# msq_ethrottle_tssop.net
KiCad netlist of a schematic drawn in EasyEDA Pro
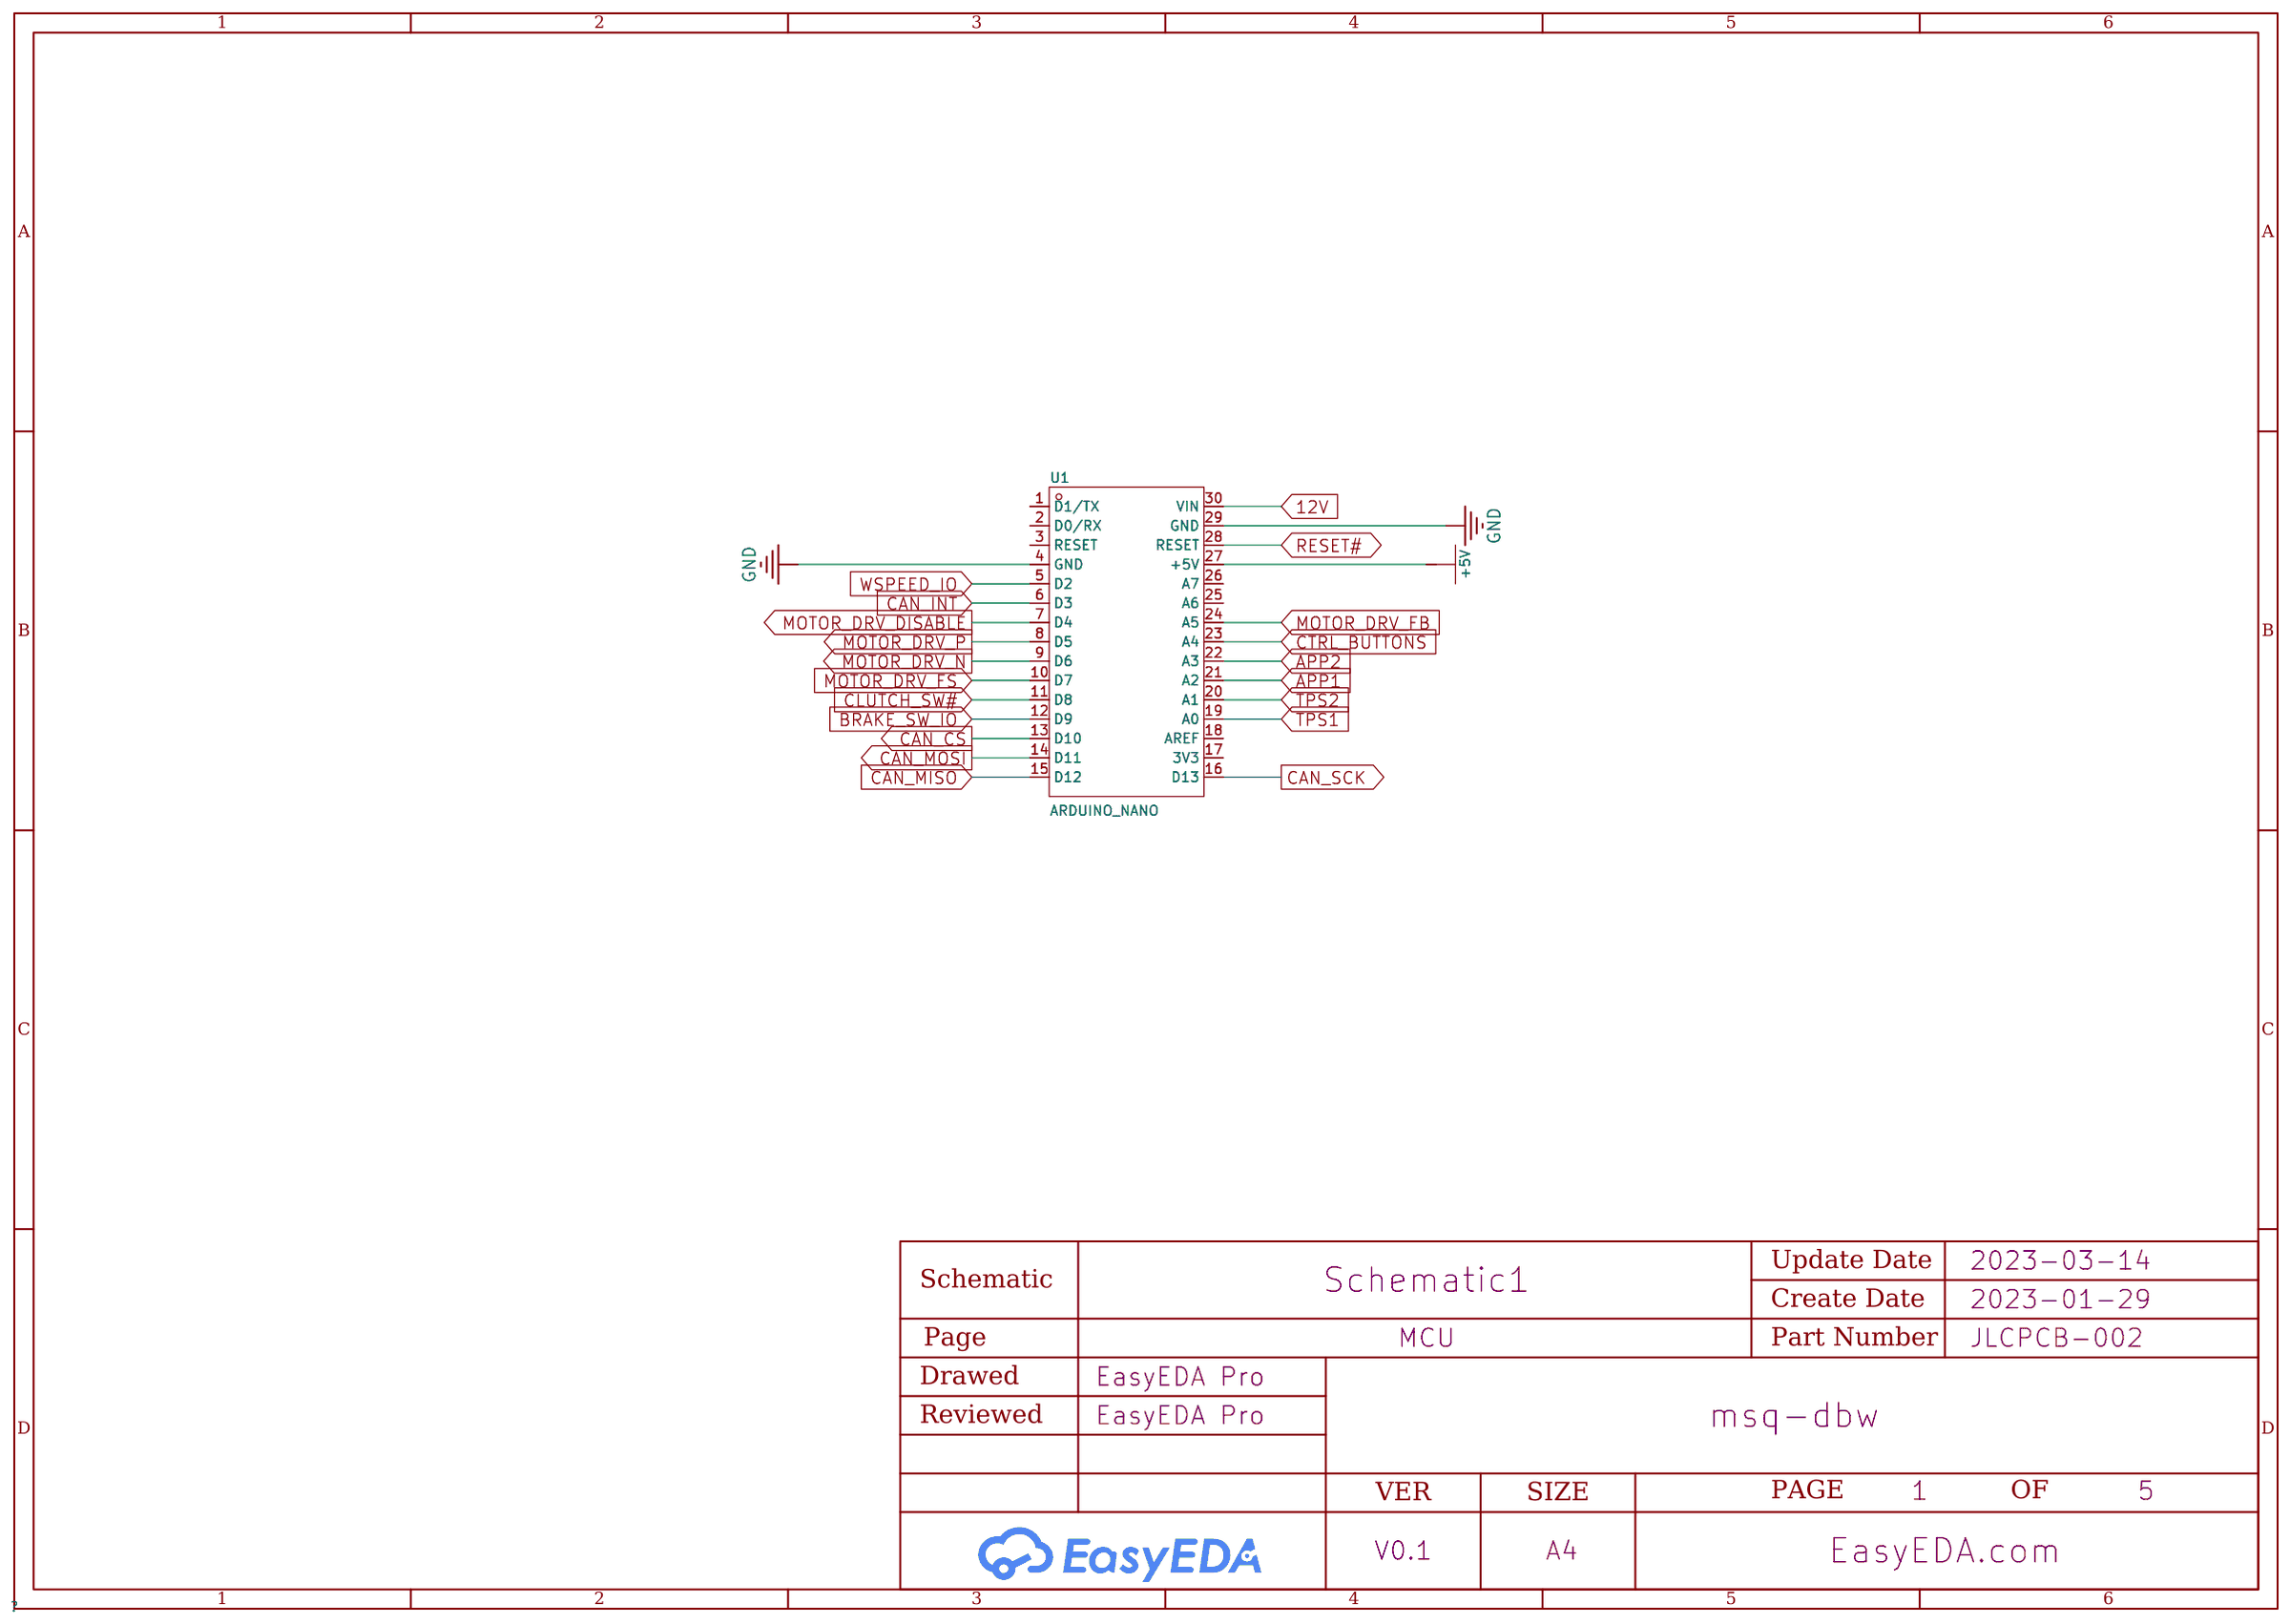
[diagram p0: MCU]
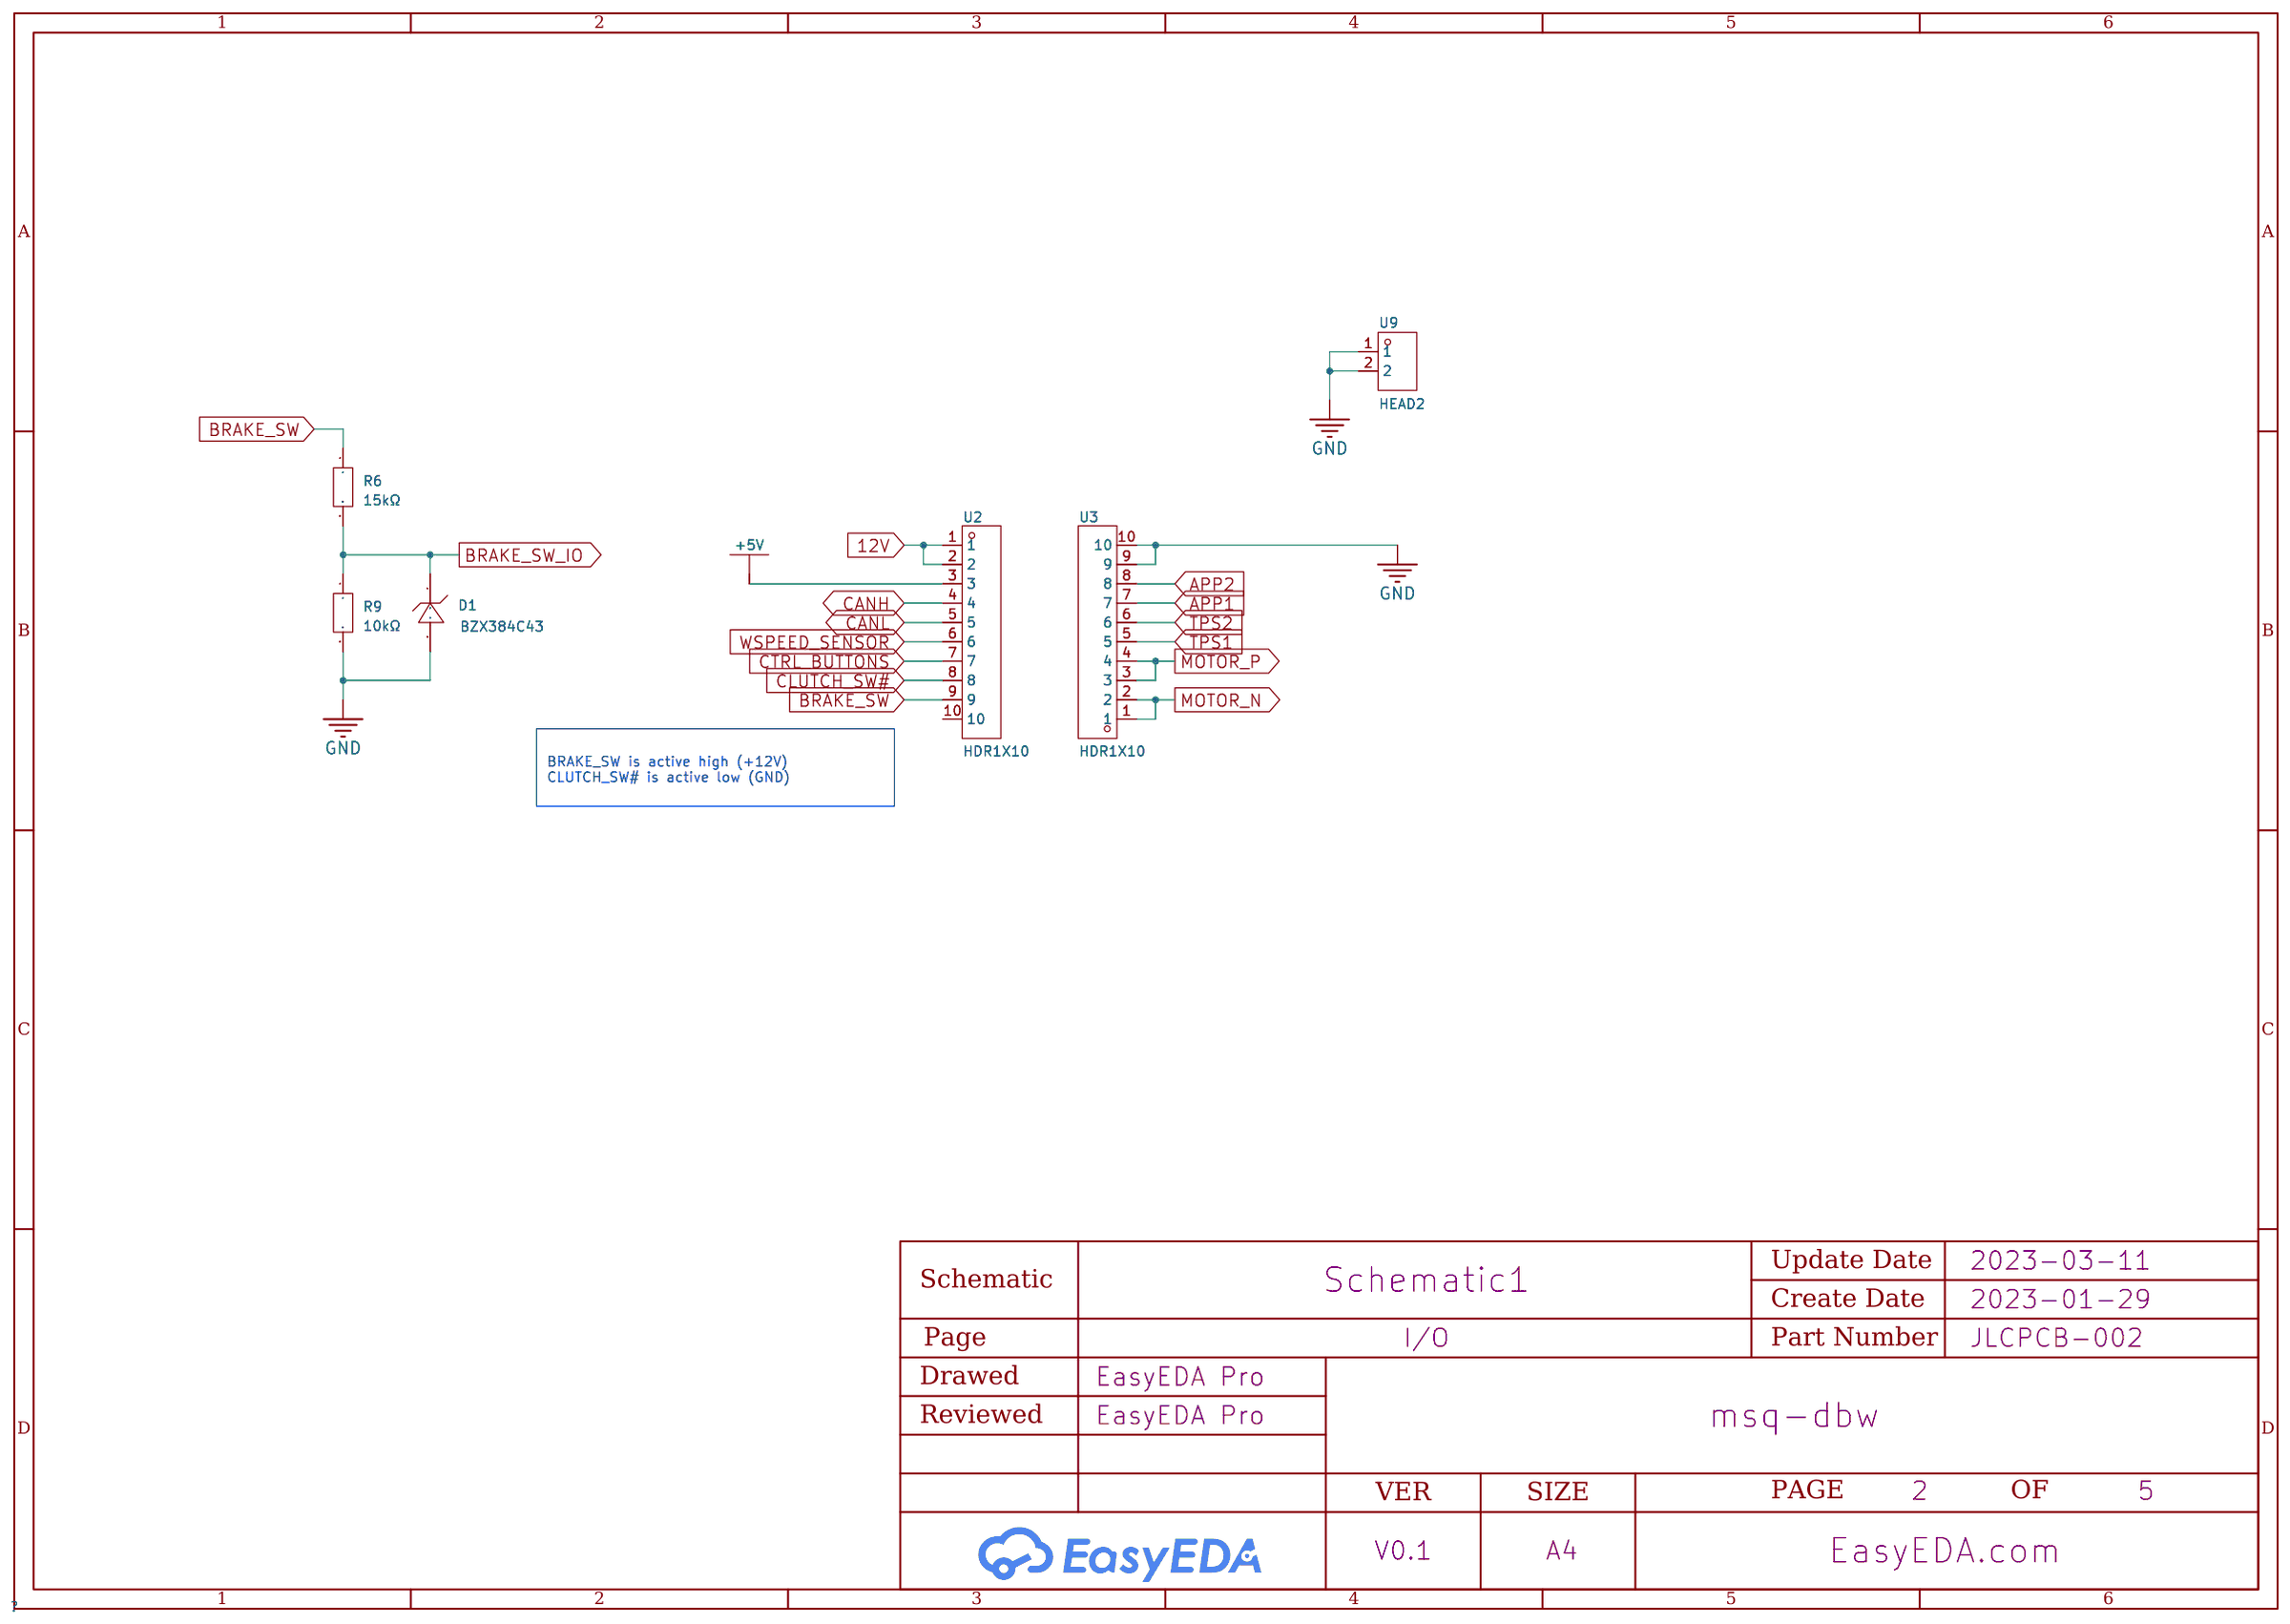
[diagram p1: I/O]
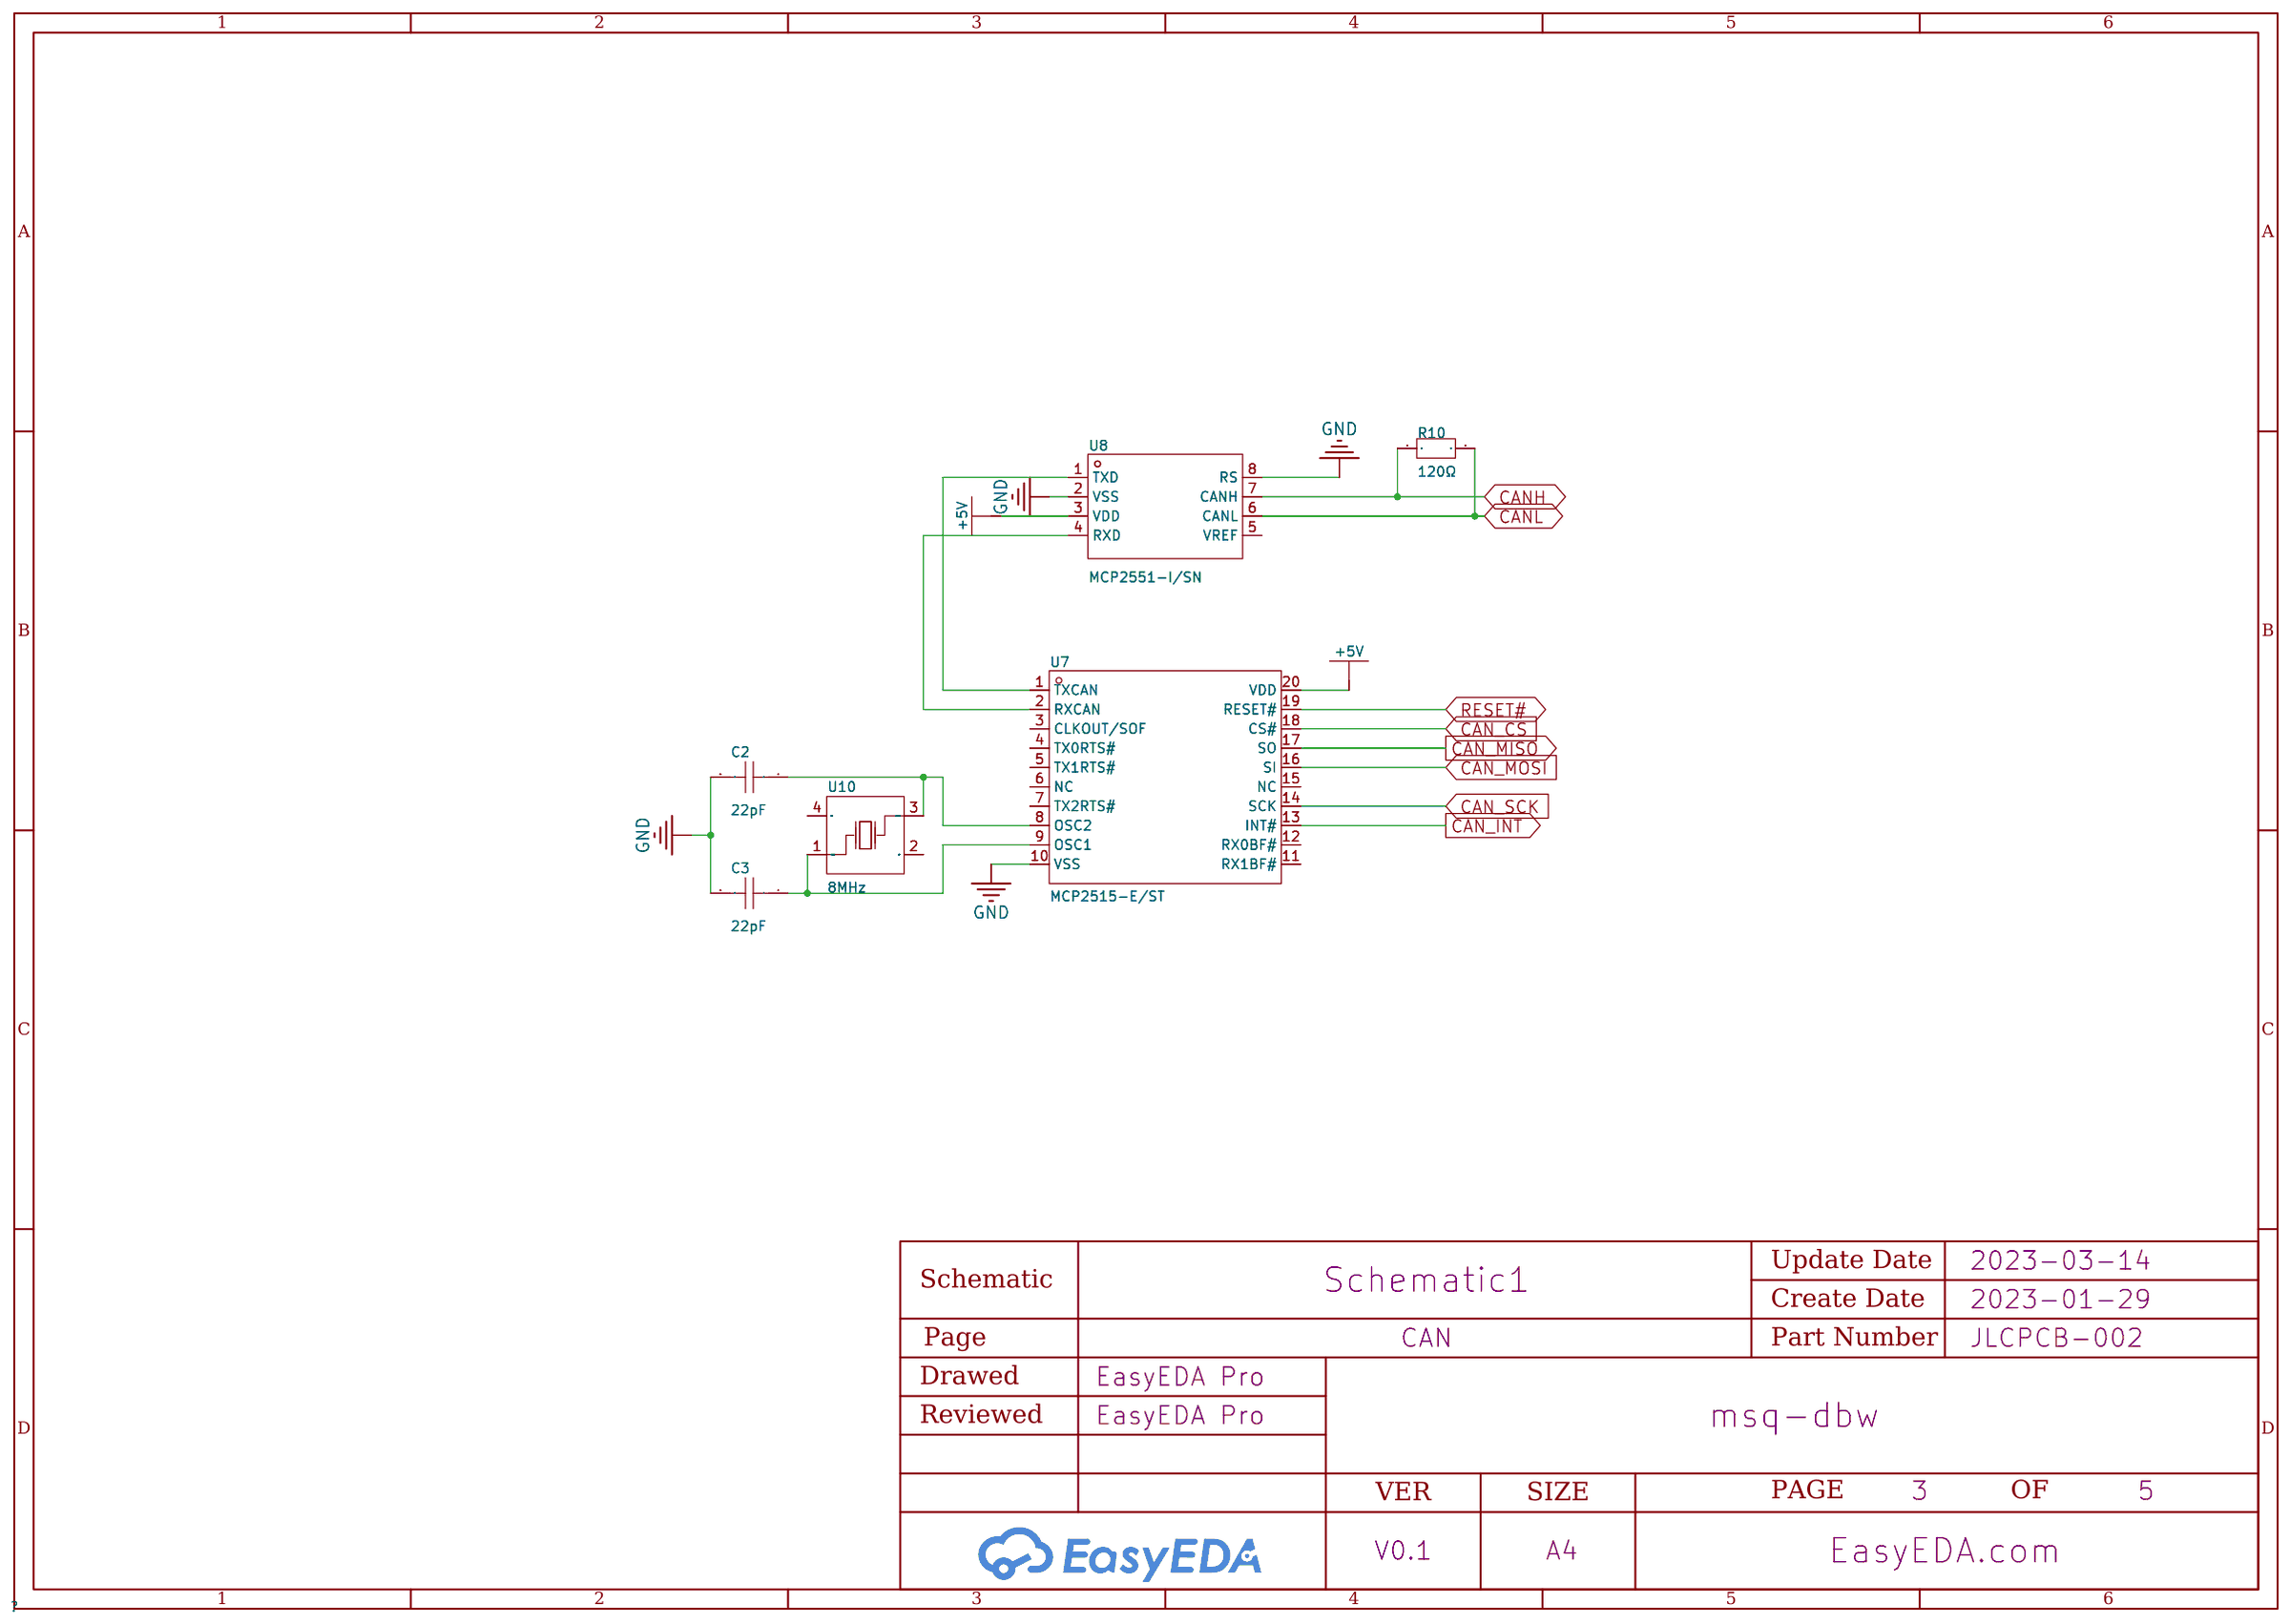
[diagram p2: CAN]
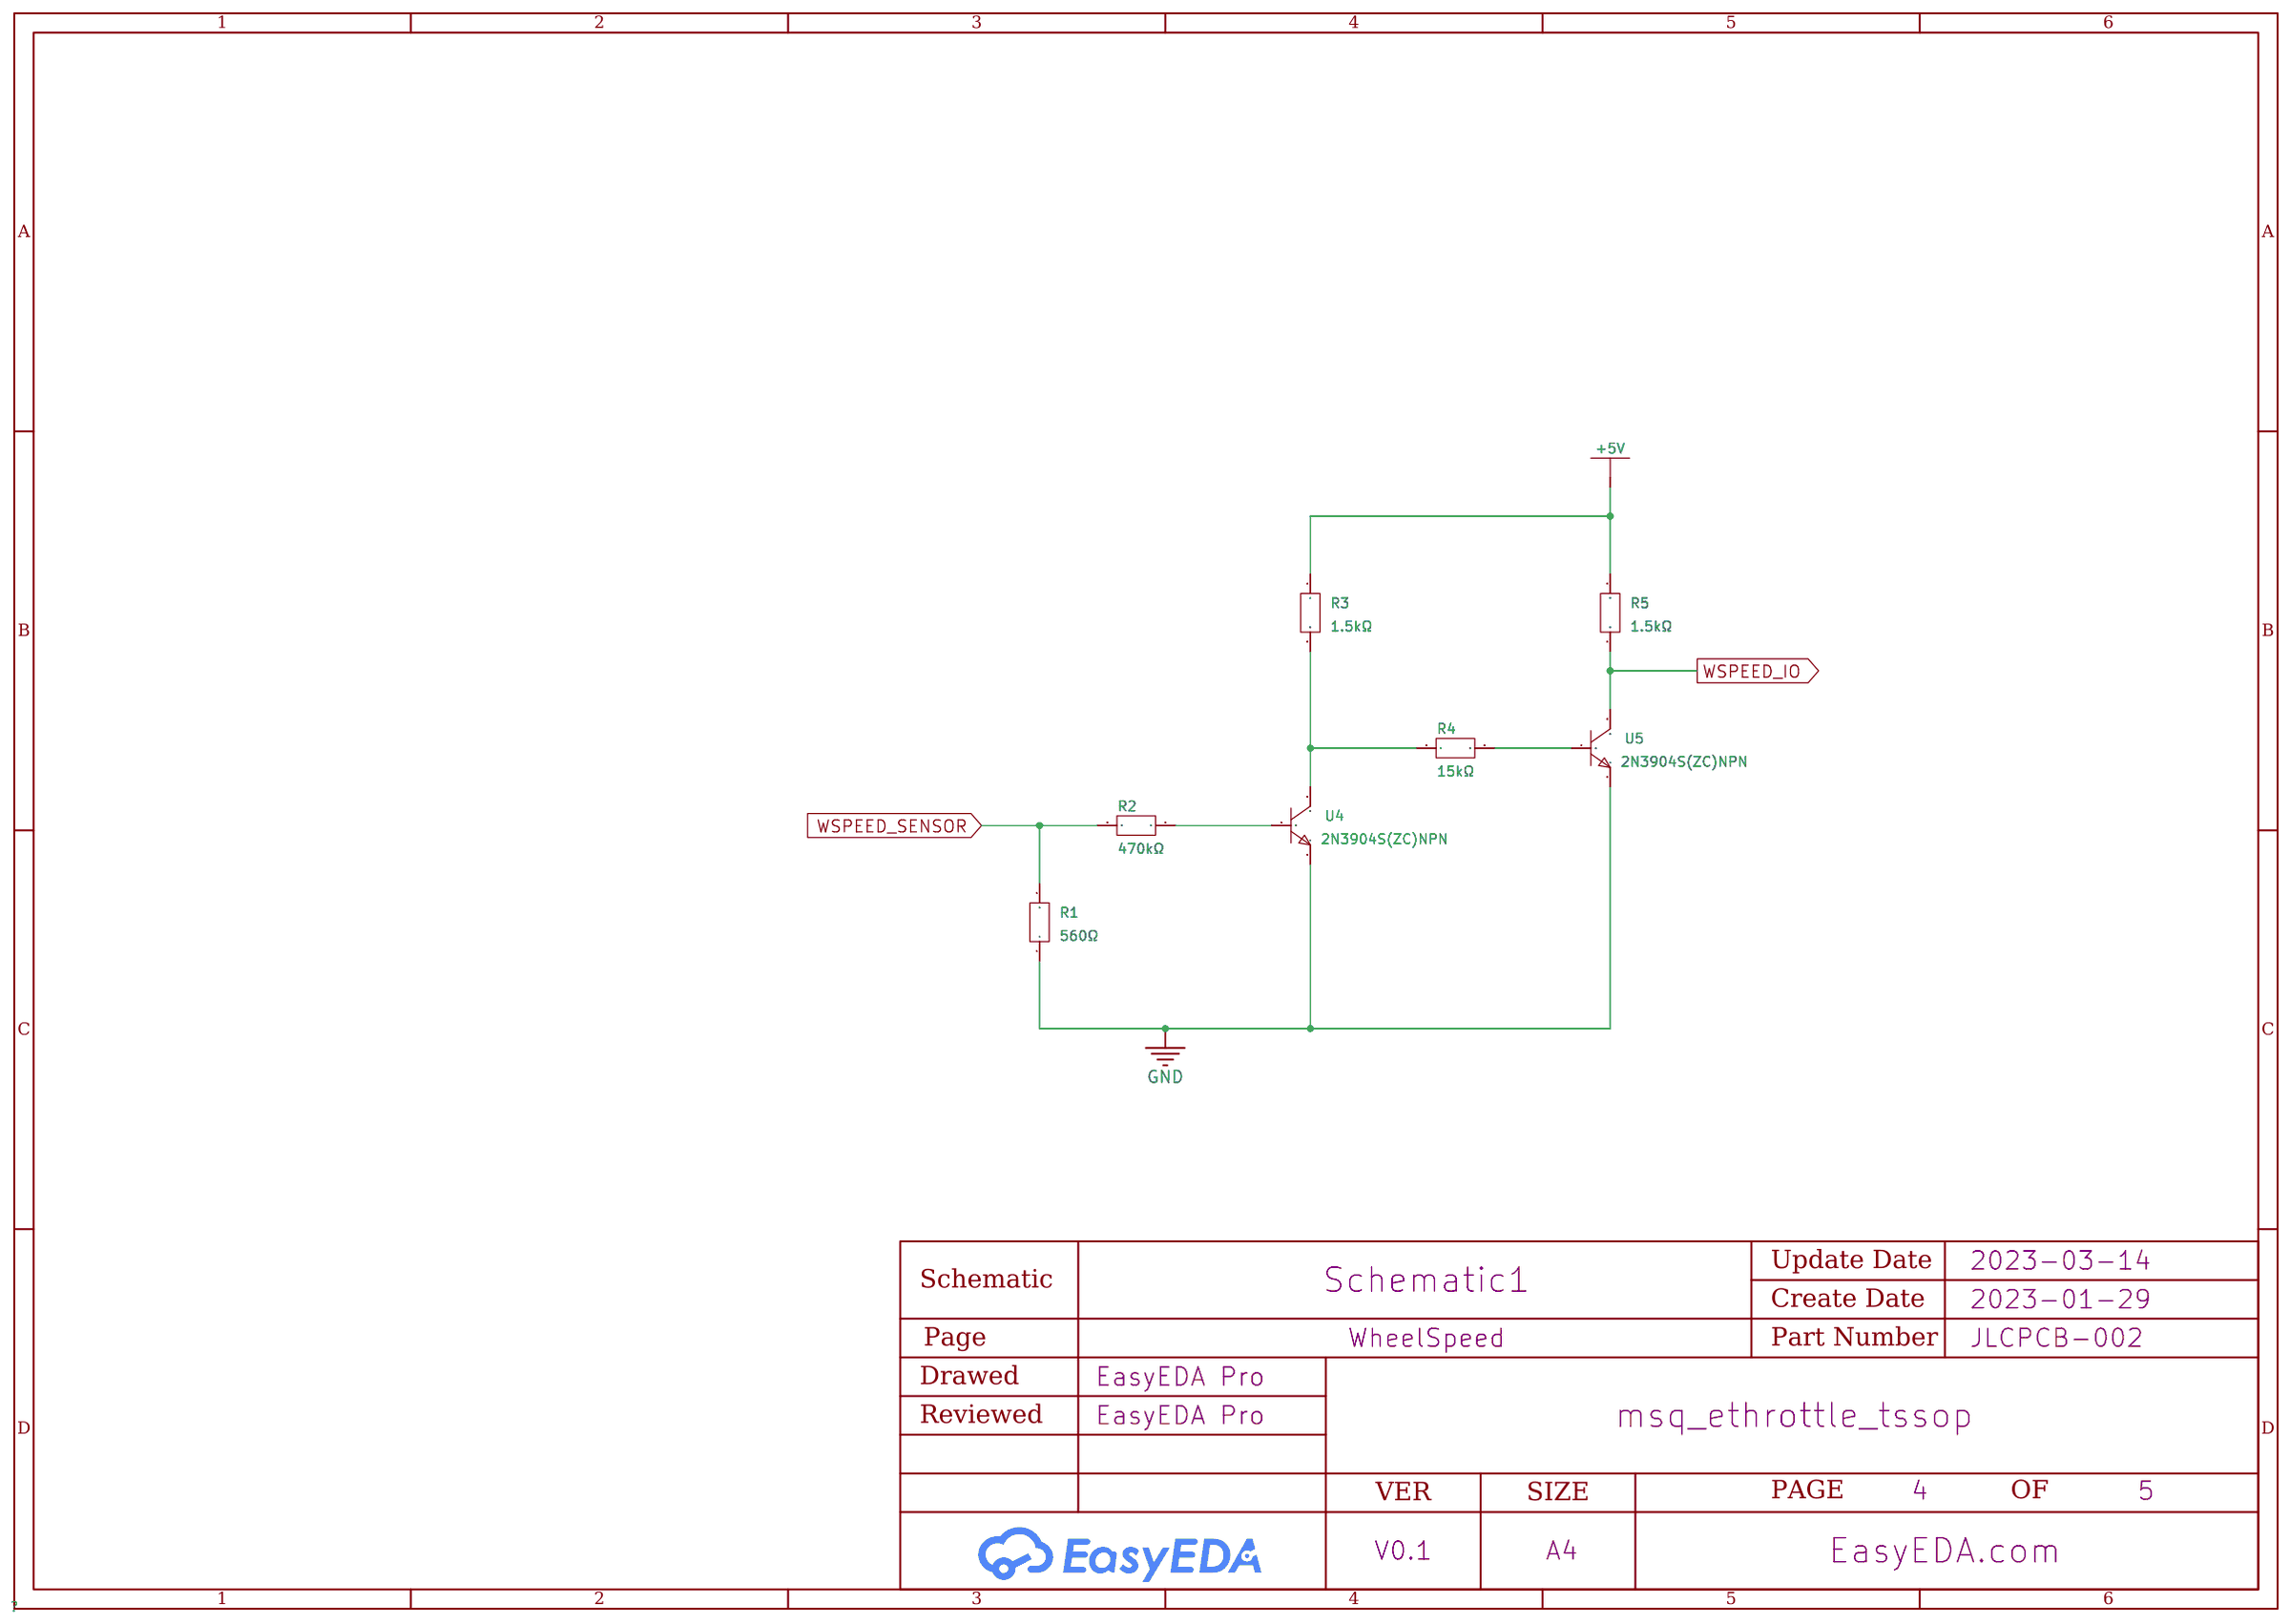
[diagram p3: WheelSpeed]
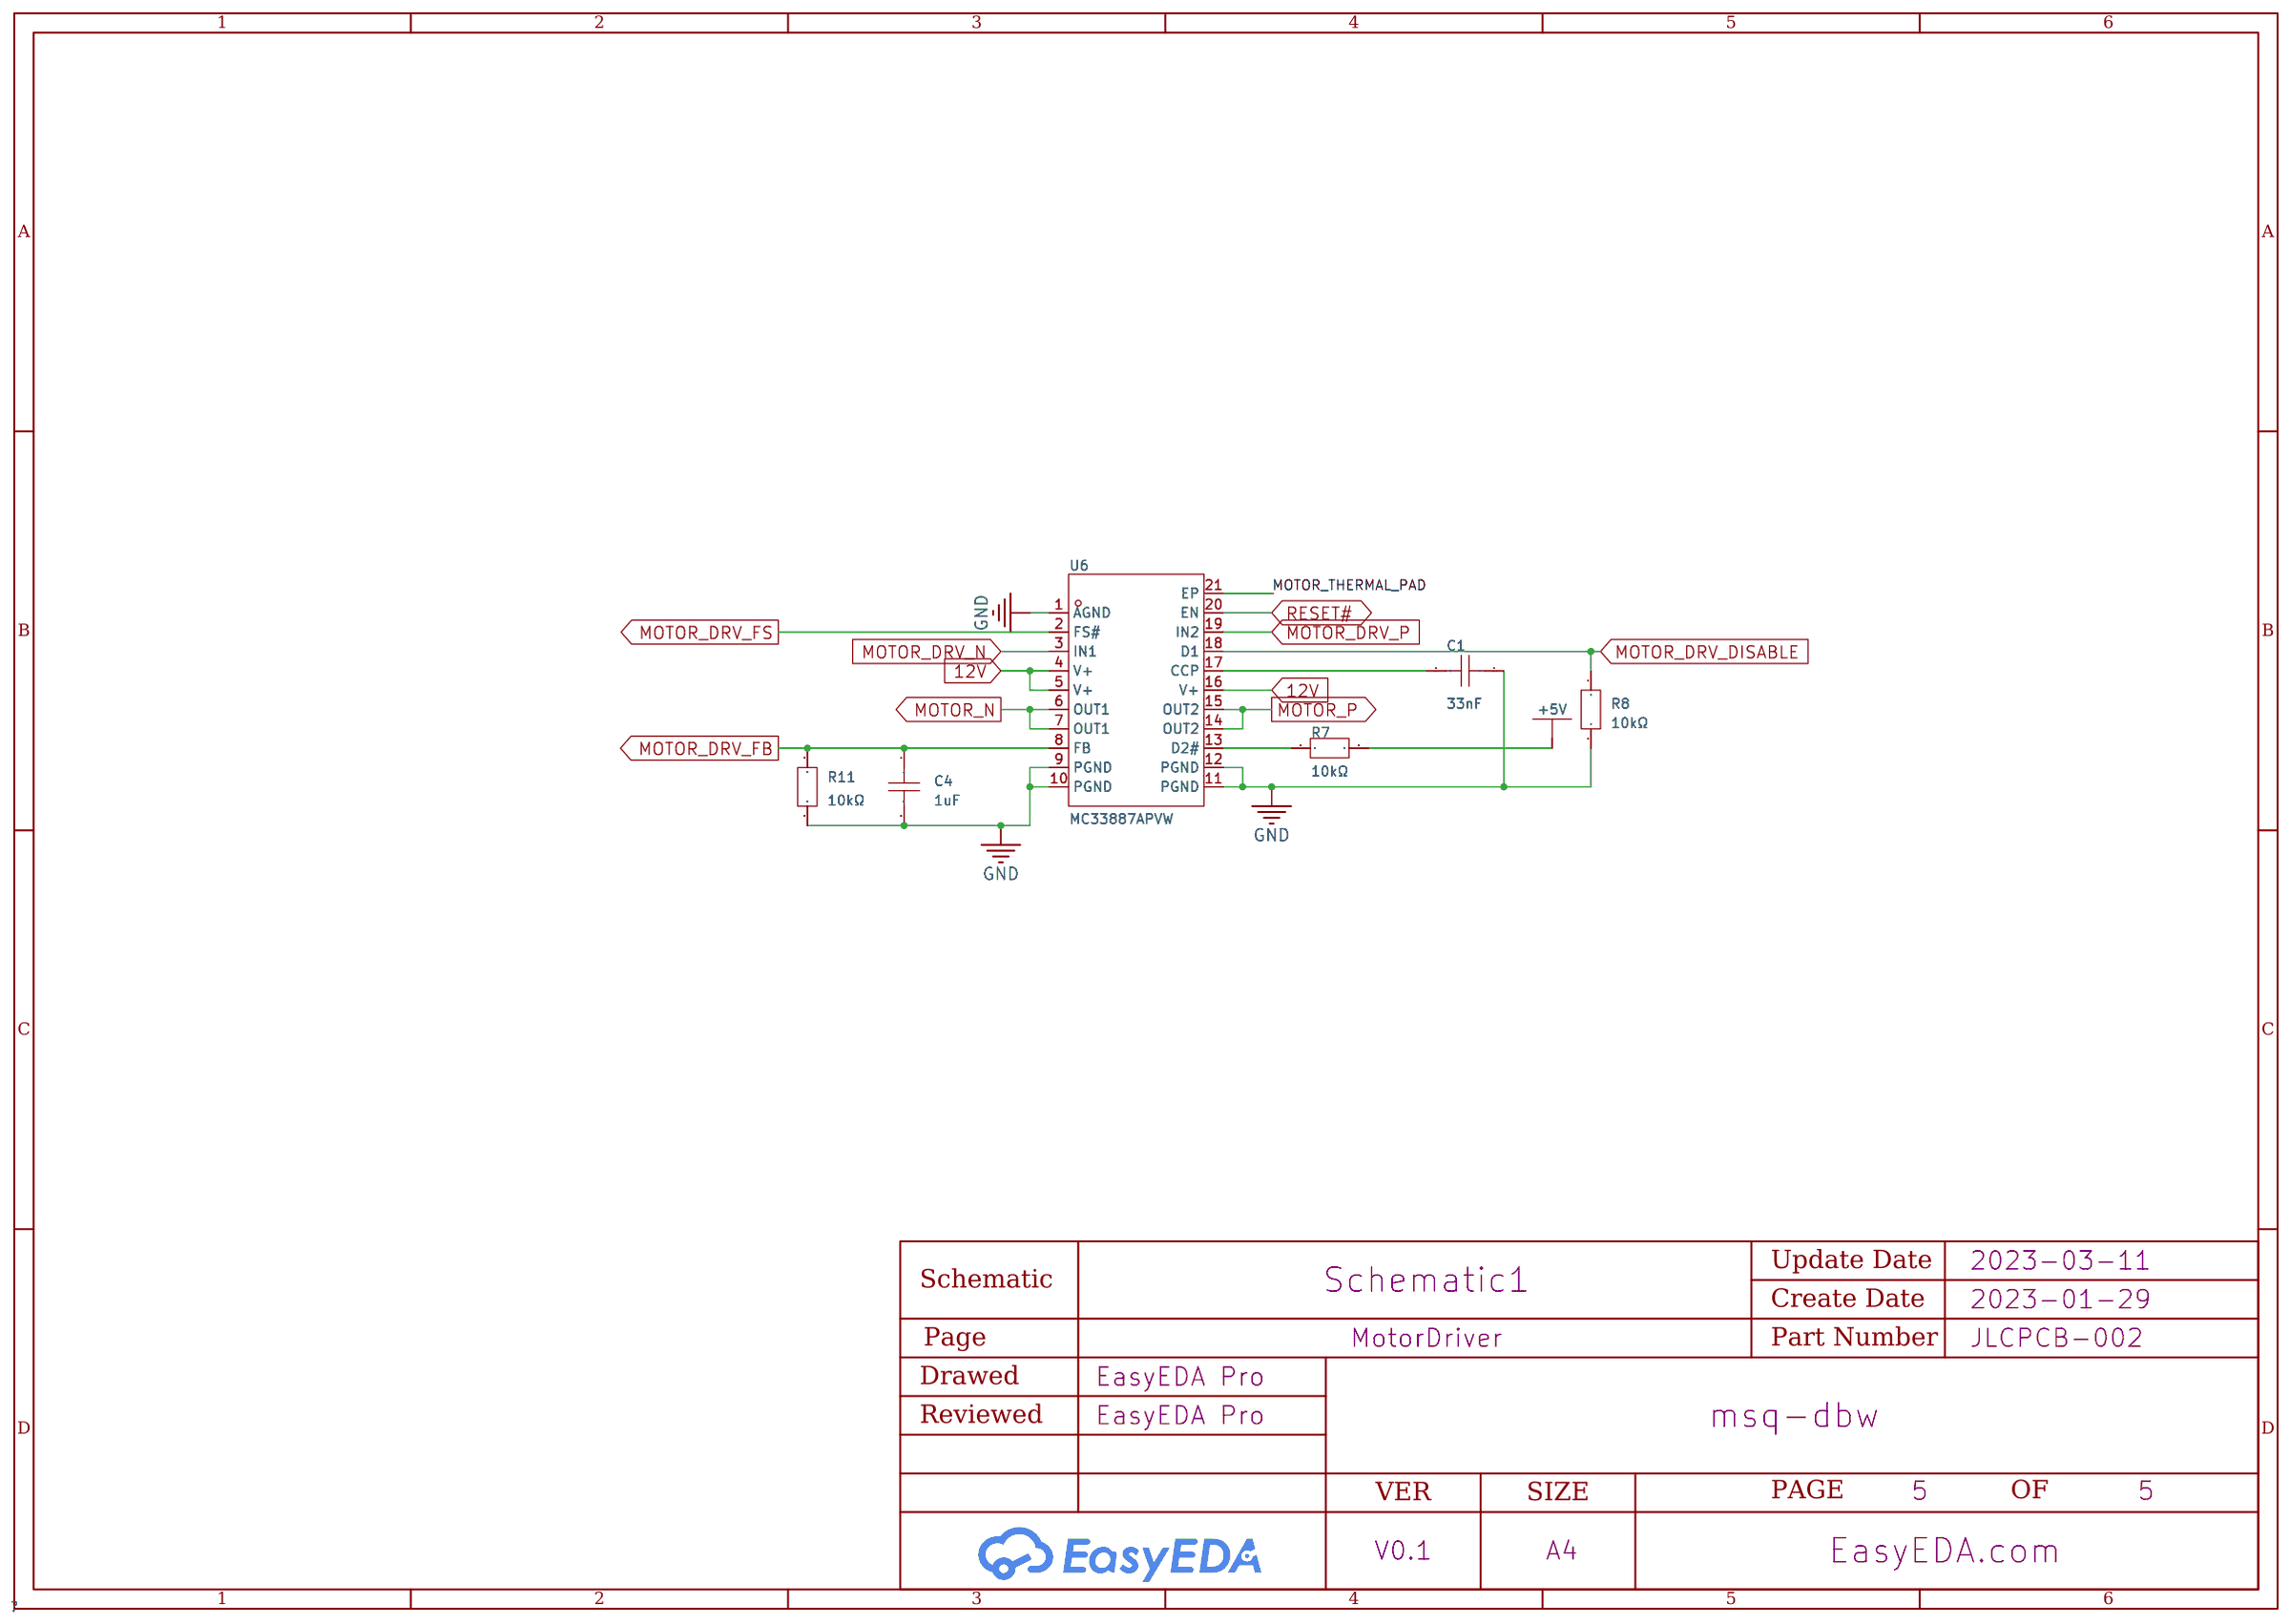
[diagram p4: MotorDriver]

(export (version "E")
  (design (tool "Eeschema 10.0.6"))
  (components
    (comp (ref "U1")
      (value "ARDUINO_NANO")
      (footprint "easyedapro:COMM-TH_ARDUINO_NANO")
      (libsource (lib "easyedapro") (part "ARDUINO_NANO"))
    )
    (comp (ref "D1")
      (value "BZX384C43")
      (footprint "easyedapro:SOD-323_L1.7-W1.3-LS2.6-RD")
      (fields (field (name "Manufacturer") "EIC") (field (name "Tolerance") "±2%"))
      (libsource (lib "easyedapro") (part "BZX384C43"))
    )
    (comp (ref "R6")
      (value "15kΩ")
      (footprint "easyedapro:R0805")
      (fields
        (field (name "Manufacturer Part") "0603WAF1002T5E")
        (field (name "Manufacturer") "UNI-ROYAL(厚声)")
        (field (name "Tolerance") "±1%")
      )
      (libsource (lib "easyedapro") (part "RT0805BRD07360RL"))
    )
    (comp (ref "R9")
      (value "10kΩ")
      (footprint "easyedapro:R0805")
      (fields
        (field (name "Manufacturer Part") "0603WAF1002T5E")
        (field (name "Manufacturer") "UNI-ROYAL(厚声)")
        (field (name "Tolerance") "±1%")
      )
      (libsource (lib "easyedapro") (part "RT0805BRD07360RL"))
    )
    (comp (ref "U2")
      (value "HDR1X10")
      (footprint "easyedapro:HDR-TH_10P-P2.54-V-F_C9900008052")
      (libsource (lib "easyedapro") (part "HDR1X10"))
    )
    (comp (ref "U3")
      (value "HDR1X10")
      (footprint "easyedapro:HDR-TH_10P-P2.54-V-F_C9900008052")
      (libsource (lib "easyedapro") (part "HDR1X10"))
    )
    (comp (ref "U9")
      (value "HEAD2")
      (footprint "easyedapro:HDR-TH_2P-P2.54-V-M")
      (libsource (lib "easyedapro") (part "HEAD2"))
    )
    (comp (ref "C2")
      (value "22pF")
      (footprint "easyedapro:C0603")
      (libsource (lib "easyedapro") (part "CAP"))
    )
    (comp (ref "C3")
      (value "22pF")
      (footprint "easyedapro:C0603")
      (libsource (lib "easyedapro") (part "CAP"))
    )
    (comp (ref "R10")
      (value "120Ω")
      (footprint "easyedapro:R0805")
      (fields
        (field (name "Manufacturer Part") "0603WAF1002T5E")
        (field (name "Manufacturer") "UNI-ROYAL(厚声)")
        (field (name "Tolerance") "±1%")
      )
      (libsource (lib "easyedapro") (part "RT0805BRD07360RL"))
    )
    (comp (ref "U7")
      (value "MCP2515-E/ST")
      (footprint "easyedapro:TSSOP-20_L6.5-W4.4-P0.65-LS6.4-BL")
      (fields (field (name "Manufacturer") "MICROCHIP(美国微芯)"))
      (libsource (lib "easyedapro") (part "MCP2515-E/ST"))
    )
    (comp (ref "U8")
      (value "MCP2551-I/SN")
      (footprint "easyedapro:SOIC-8_L4.9-W3.9-P1.27-LS6.0-BL")
      (description "Type:Transceiver Supply Voltage:4.5V~5.5V Supply Voltage:4.5V~5.5V")
      (fields (field (name "Manufacturer") "MICROCHIP(美国微芯)"))
      (libsource (lib "easyedapro") (part "MCP2551-I/SN"))
    )
    (comp (ref "U10")
      (value "8MHz")
      (footprint "easyedapro:CRYSTAL-SMD_4P-L3.2-W2.5-BL")
      (fields (field (name "Manufacturer Part") "L327S270S11L") (field (name "Manufacturer") "Lucki(蓝晶)"))
      (libsource (lib "easyedapro") (part "L327S270S11L"))
    )
    (comp (ref "R1")
      (value "560Ω")
      (footprint "easyedapro:R0805")
      (fields
        (field (name "Manufacturer Part") "0603WAF1002T5E")
        (field (name "Manufacturer") "UNI-ROYAL(厚声)")
        (field (name "Tolerance") "±1%")
      )
      (libsource (lib "easyedapro") (part "RT0805BRD07360RL"))
    )
    (comp (ref "R2")
      (value "470kΩ")
      (footprint "easyedapro:R0805")
      (fields
        (field (name "Manufacturer Part") "0603WAF1002T5E")
        (field (name "Manufacturer") "UNI-ROYAL(厚声)")
        (field (name "Tolerance") "±1%")
      )
      (libsource (lib "easyedapro") (part "RT0805BRD07360RL"))
    )
    (comp (ref "R3")
      (value "1.5kΩ")
      (footprint "easyedapro:R0805")
      (fields
        (field (name "Manufacturer Part") "0603WAF1002T5E")
        (field (name "Manufacturer") "UNI-ROYAL(厚声)")
        (field (name "Tolerance") "±1%")
      )
      (libsource (lib "easyedapro") (part "RT0805BRD07360RL"))
    )
    (comp (ref "R4")
      (value "15kΩ")
      (footprint "easyedapro:R0805")
      (fields
        (field (name "Manufacturer Part") "0603WAF1002T5E")
        (field (name "Manufacturer") "UNI-ROYAL(厚声)")
        (field (name "Tolerance") "±1%")
      )
      (libsource (lib "easyedapro") (part "RT0805BRD07360RL"))
    )
    (comp (ref "R5")
      (value "1.5kΩ")
      (footprint "easyedapro:R0805")
      (fields
        (field (name "Manufacturer Part") "0603WAF1002T5E")
        (field (name "Manufacturer") "UNI-ROYAL(厚声)")
        (field (name "Tolerance") "±1%")
      )
      (libsource (lib "easyedapro") (part "RT0805BRD07360RL"))
    )
    (comp (ref "U4")
      (value "2N3904S(ZC)NPN")
      (footprint "easyedapro:SOT-23-3_L2.9-W1.3-P0.95-LS2.4-BR")
      (libsource (lib "easyedapro") (part "2N3904S(ZC)NPN"))
    )
    (comp (ref "U5")
      (value "2N3904S(ZC)NPN")
      (footprint "easyedapro:SOT-23-3_L2.9-W1.3-P0.95-LS2.4-BR")
      (libsource (lib "easyedapro") (part "2N3904S(ZC)NPN"))
    )
    (comp (ref "C1")
      (value "33nF")
      (footprint "easyedapro:C0603")
      (libsource (lib "easyedapro") (part "CAP"))
    )
    (comp (ref "C4") (value "1uF") (footprint "easyedapro:C0603") (libsource (lib "easyedapro") (part "CAP")))
    (comp (ref "R7")
      (value "10kΩ")
      (footprint "easyedapro:R0805")
      (fields
        (field (name "Manufacturer Part") "0603WAF1002T5E")
        (field (name "Manufacturer") "UNI-ROYAL(厚声)")
        (field (name "Tolerance") "±1%")
      )
      (libsource (lib "easyedapro") (part "RT0805BRD07360RL"))
    )
    (comp (ref "R8")
      (value "10kΩ")
      (footprint "easyedapro:R0805")
      (fields
        (field (name "Manufacturer Part") "0603WAF1002T5E")
        (field (name "Manufacturer") "UNI-ROYAL(厚声)")
        (field (name "Tolerance") "±1%")
      )
      (libsource (lib "easyedapro") (part "RT0805BRD07360RL"))
    )
    (comp (ref "R11")
      (value "10kΩ")
      (footprint "easyedapro:R0805")
      (fields
        (field (name "Manufacturer Part") "0603WAF1002T5E")
        (field (name "Manufacturer") "UNI-ROYAL(厚声)")
        (field (name "Tolerance") "±1%")
      )
      (libsource (lib "easyedapro") (part "RT0805BRD07360RL"))
    )
    (comp (ref "U6")
      (value "MC33887APVW")
      (footprint "easyedapro:HSOP-20_L15.9-W11.0-P1.27-LS14.2-TL-EP")
      (fields (field (name "Manufacturer") "NXP(恩智浦)"))
      (libsource (lib "easyedapro") (part "MC33887APVW"))
    )
  )
  (nets
    (net (code "1") (name "+5V") (class "Default")
      (node (ref "R3") (pin "1") (pinfunction "1_1") (pintype "input"))
      (node (ref "R5") (pin "2") (pinfunction "2_2") (pintype "input"))
      (node (ref "R7") (pin "1") (pinfunction "1_1") (pintype "input"))
      (node (ref "U1") (pin "27") (pinfunction "+5V_27") (pintype "input"))
      (node (ref "U2") (pin "3") (pinfunction "3_3") (pintype "input"))
      (node (ref "U7") (pin "20") (pinfunction "VDD_20") (pintype "input"))
      (node (ref "U8") (pin "3") (pinfunction "VDD_3") (pintype "input"))
    )
    (net (code "2") (name "12V") (class "Default")
      (node (ref "U1") (pin "30") (pinfunction "VIN_30") (pintype "input"))
      (node (ref "U2") (pin "1") (pinfunction "1_1") (pintype "input"))
      (node (ref "U2") (pin "2") (pinfunction "2_2") (pintype "input"))
      (node (ref "U6") (pin "16") (pinfunction "V+_16") (pintype "input"))
      (node (ref "U6") (pin "4") (pinfunction "V+_4") (pintype "input"))
      (node (ref "U6") (pin "5") (pinfunction "V+_5") (pintype "input"))
    )
    (net (code "3") (name "APP1") (class "Default")
      (node (ref "U1") (pin "21") (pinfunction "A2_21") (pintype "input"))
      (node (ref "U3") (pin "7") (pinfunction "7_7") (pintype "input"))
    )
    (net (code "4") (name "APP2") (class "Default")
      (node (ref "U1") (pin "22") (pinfunction "A3_22") (pintype "input"))
      (node (ref "U3") (pin "8") (pinfunction "8_8") (pintype "input"))
    )
    (net (code "5") (name "BRAKE_SW") (class "Default")
      (node (ref "R6") (pin "1") (pinfunction "1_1") (pintype "input"))
      (node (ref "U2") (pin "9") (pinfunction "9_9") (pintype "input"))
    )
    (net (code "6") (name "BRAKE_SW_IO") (class "Default")
      (node (ref "D1") (pin "1") (pinfunction "C_1") (pintype "input"))
      (node (ref "R6") (pin "2") (pinfunction "2_2") (pintype "input"))
      (node (ref "R9") (pin "1") (pinfunction "1_1") (pintype "input"))
      (node (ref "U1") (pin "12") (pinfunction "D9_12") (pintype "input"))
    )
    (net (code "7") (name "CANH") (class "Default")
      (node (ref "R10") (pin "1") (pinfunction "1_1") (pintype "input"))
      (node (ref "U2") (pin "4") (pinfunction "4_4") (pintype "input"))
      (node (ref "U8") (pin "7") (pinfunction "CANH_7") (pintype "input"))
    )
    (net (code "8") (name "CANL") (class "Default")
      (node (ref "R10") (pin "2") (pinfunction "2_2") (pintype "input"))
      (node (ref "U2") (pin "5") (pinfunction "5_5") (pintype "input"))
      (node (ref "U8") (pin "6") (pinfunction "CANL_6") (pintype "input"))
    )
    (net (code "9") (name "CAN_CS") (class "Default")
      (node (ref "U1") (pin "13") (pinfunction "D10_13") (pintype "input"))
      (node (ref "U7") (pin "18") (pinfunction "CS#_18") (pintype "input"))
    )
    (net (code "10") (name "CAN_INT") (class "Default")
      (node (ref "U1") (pin "6") (pinfunction "D3_6") (pintype "input"))
      (node (ref "U7") (pin "13") (pinfunction "INT#_13") (pintype "input"))
    )
    (net (code "11") (name "CAN_MISO") (class "Default")
      (node (ref "U1") (pin "15") (pinfunction "D12_15") (pintype "input"))
      (node (ref "U7") (pin "17") (pinfunction "SO_17") (pintype "input"))
    )
    (net (code "12") (name "CAN_MOSI") (class "Default")
      (node (ref "U1") (pin "14") (pinfunction "D11_14") (pintype "input"))
      (node (ref "U7") (pin "16") (pinfunction "SI_16") (pintype "input"))
    )
    (net (code "13") (name "CAN_SCK") (class "Default")
      (node (ref "U1") (pin "16") (pinfunction "D13_16") (pintype "input"))
      (node (ref "U7") (pin "14") (pinfunction "SCK_14") (pintype "input"))
    )
    (net (code "14") (name "CLUTCH_SW#") (class "Default")
      (node (ref "U1") (pin "11") (pinfunction "D8_11") (pintype "input"))
      (node (ref "U2") (pin "8") (pinfunction "8_8") (pintype "input"))
    )
    (net (code "15") (name "CTRL_BUTTONS") (class "Default")
      (node (ref "U1") (pin "23") (pinfunction "A4_23") (pintype "input"))
      (node (ref "U2") (pin "7") (pinfunction "7_7") (pintype "input"))
    )
    (net (code "16") (name "GND") (class "Default")
      (node (ref "C1") (pin "1") (pinfunction "1_1") (pintype "input"))
      (node (ref "C2") (pin "2") (pinfunction "2_2") (pintype "input"))
      (node (ref "C3") (pin "2") (pinfunction "2_2") (pintype "input"))
      (node (ref "C4") (pin "2") (pinfunction "2_2") (pintype "input"))
      (node (ref "D1") (pin "2") (pinfunction "A_2") (pintype "input"))
      (node (ref "R1") (pin "1") (pinfunction "1_1") (pintype "input"))
      (node (ref "R11") (pin "1") (pinfunction "1_1") (pintype "input"))
      (node (ref "R8") (pin "2") (pinfunction "2_2") (pintype "input"))
      (node (ref "R9") (pin "2") (pinfunction "2_2") (pintype "input"))
      (node (ref "U1") (pin "29") (pinfunction "GND_29") (pintype "input"))
      (node (ref "U1") (pin "4") (pinfunction "GND_4") (pintype "input"))
      (node (ref "U3") (pin "10") (pinfunction "10_10") (pintype "input"))
      (node (ref "U3") (pin "9") (pinfunction "9_9") (pintype "input"))
      (node (ref "U4") (pin "2") (pinfunction "E_2") (pintype "input"))
      (node (ref "U5") (pin "2") (pinfunction "E_2") (pintype "input"))
      (node (ref "U6") (pin "1") (pinfunction "AGND_1") (pintype "input"))
      (node (ref "U6") (pin "10") (pinfunction "PGND_10") (pintype "input"))
      (node (ref "U6") (pin "11") (pinfunction "PGND_11") (pintype "input"))
      (node (ref "U6") (pin "12") (pinfunction "PGND_12") (pintype "input"))
      (node (ref "U6") (pin "9") (pinfunction "PGND_9") (pintype "input"))
      (node (ref "U7") (pin "10") (pinfunction "VSS_10") (pintype "input"))
      (node (ref "U8") (pin "2") (pinfunction "VSS_2") (pintype "input"))
      (node (ref "U8") (pin "8") (pinfunction "RS_8") (pintype "input"))
      (node (ref "U9") (pin "1") (pinfunction "1_1") (pintype "input"))
      (node (ref "U9") (pin "2") (pinfunction "2_2") (pintype "input"))
    )
    (net (code "17") (name "MOTOR_DRV_DISABLE") (class "Default")
      (node (ref "R8") (pin "1") (pinfunction "1_1") (pintype "input"))
      (node (ref "U1") (pin "7") (pinfunction "D4_7") (pintype "input"))
      (node (ref "U6") (pin "18") (pinfunction "D1_18") (pintype "input"))
    )
    (net (code "18") (name "MOTOR_DRV_FB") (class "Default")
      (node (ref "C4") (pin "1") (pinfunction "1_1") (pintype "input"))
      (node (ref "R11") (pin "2") (pinfunction "2_2") (pintype "input"))
      (node (ref "U1") (pin "24") (pinfunction "A5_24") (pintype "input"))
      (node (ref "U6") (pin "8") (pinfunction "FB_8") (pintype "input"))
    )
    (net (code "19") (name "MOTOR_DRV_FS") (class "Default")
      (node (ref "U1") (pin "10") (pinfunction "D7_10") (pintype "input"))
      (node (ref "U6") (pin "2") (pinfunction "FS#_2") (pintype "input"))
    )
    (net (code "20") (name "MOTOR_DRV_N") (class "Default")
      (node (ref "U1") (pin "9") (pinfunction "D6_9") (pintype "input"))
      (node (ref "U6") (pin "3") (pinfunction "IN1_3") (pintype "input"))
    )
    (net (code "21") (name "MOTOR_DRV_P") (class "Default")
      (node (ref "U1") (pin "8") (pinfunction "D5_8") (pintype "input"))
      (node (ref "U6") (pin "19") (pinfunction "IN2_19") (pintype "input"))
    )
    (net (code "22") (name "MOTOR_N") (class "Default")
      (node (ref "U3") (pin "1") (pinfunction "1_1") (pintype "input"))
      (node (ref "U3") (pin "2") (pinfunction "2_2") (pintype "input"))
      (node (ref "U6") (pin "6") (pinfunction "OUT1_6") (pintype "input"))
      (node (ref "U6") (pin "7") (pinfunction "OUT1_7") (pintype "input"))
    )
    (net (code "23") (name "MOTOR_P") (class "Default")
      (node (ref "U3") (pin "3") (pinfunction "3_3") (pintype "input"))
      (node (ref "U3") (pin "4") (pinfunction "4_4") (pintype "input"))
      (node (ref "U6") (pin "14") (pinfunction "OUT2_14") (pintype "input"))
      (node (ref "U6") (pin "15") (pinfunction "OUT2_15") (pintype "input"))
    )
    (net (code "24") (name "MOTOR_THERMAL_PAD") (class "Default")
      (node (ref "U6") (pin "21") (pinfunction "EP_21") (pintype "input"))
    )
    (net (code "25") (name "Net-(U4-B)") (class "Default")
      (node (ref "R2") (pin "1") (pinfunction "1_1") (pintype "input"))
      (node (ref "U4") (pin "1") (pinfunction "B_1") (pintype "input"))
    )
    (net (code "26") (name "Net-(U4-C)") (class "Default")
      (node (ref "R3") (pin "2") (pinfunction "2_2") (pintype "input"))
      (node (ref "R4") (pin "1") (pinfunction "1_1") (pintype "input"))
      (node (ref "U4") (pin "3") (pinfunction "C_3") (pintype "input"))
    )
    (net (code "27") (name "Net-(U5-B)") (class "Default")
      (node (ref "R4") (pin "2") (pinfunction "2_2") (pintype "input"))
      (node (ref "U5") (pin "1") (pinfunction "B_1") (pintype "input"))
    )
    (net (code "28") (name "Net-(U6-CCP)") (class "Default")
      (node (ref "C1") (pin "2") (pinfunction "2_2") (pintype "input"))
      (node (ref "U6") (pin "17") (pinfunction "CCP_17") (pintype "input"))
    )
    (net (code "29") (name "Net-(U6-D2#)") (class "Default")
      (node (ref "R7") (pin "2") (pinfunction "2_2") (pintype "input"))
      (node (ref "U6") (pin "13") (pinfunction "D2#_13") (pintype "input"))
    )
    (net (code "30") (name "Net-(U7-RXCAN)") (class "Default")
      (node (ref "U7") (pin "2") (pinfunction "RXCAN_2") (pintype "input"))
      (node (ref "U8") (pin "4") (pinfunction "RXD_4") (pintype "input"))
    )
    (net (code "31") (name "Net-(U7-TXCAN)") (class "Default")
      (node (ref "U7") (pin "1") (pinfunction "TXCAN_1") (pintype "input"))
      (node (ref "U8") (pin "1") (pinfunction "TXD_1") (pintype "input"))
    )
    (net (code "32") (name "Net-(U10-Xtal_Terminal_(Input))") (class "Default")
      (node (ref "C3") (pin "1") (pinfunction "1_1") (pintype "input"))
      (node (ref "U10") (pin "1") (pinfunction "Xtal_Terminal_(Input)_1") (pintype "input"))
      (node (ref "U7") (pin "9") (pinfunction "OSC1_9") (pintype "input"))
    )
    (net (code "33") (name "Net-(U10-Xtal_Terminal_(Output))") (class "Default")
      (node (ref "C2") (pin "1") (pinfunction "1_1") (pintype "input"))
      (node (ref "U10") (pin "3") (pinfunction "Xtal_Terminal_(Output)_3") (pintype "input"))
      (node (ref "U7") (pin "8") (pinfunction "OSC2_8") (pintype "input"))
    )
    (net (code "34") (name "RESET#") (class "Default")
      (node (ref "U1") (pin "28") (pinfunction "RESET_28") (pintype "input"))
      (node (ref "U6") (pin "20") (pinfunction "EN_20") (pintype "input"))
      (node (ref "U7") (pin "19") (pinfunction "RESET#_19") (pintype "input"))
    )
    (net (code "35") (name "TPS1") (class "Default")
      (node (ref "U1") (pin "19") (pinfunction "A0_19") (pintype "input"))
      (node (ref "U3") (pin "5") (pinfunction "5_5") (pintype "input"))
    )
    (net (code "36") (name "TPS2") (class "Default")
      (node (ref "U1") (pin "20") (pinfunction "A1_20") (pintype "input"))
      (node (ref "U3") (pin "6") (pinfunction "6_6") (pintype "input"))
    )
    (net (code "37") (name "WSPEED_IO") (class "Default")
      (node (ref "R5") (pin "1") (pinfunction "1_1") (pintype "input"))
      (node (ref "U1") (pin "5") (pinfunction "D2_5") (pintype "input"))
      (node (ref "U5") (pin "3") (pinfunction "C_3") (pintype "input"))
    )
    (net (code "38") (name "WSPEED_SENSOR") (class "Default")
      (node (ref "R1") (pin "2") (pinfunction "2_2") (pintype "input"))
      (node (ref "R2") (pin "2") (pinfunction "2_2") (pintype "input"))
      (node (ref "U2") (pin "6") (pinfunction "6_6") (pintype "input"))
    )
    (net (code "39") (name "unconnected-(U1-3V3-Pad17)") (class "Default")
      (node (ref "U1") (pin "17") (pinfunction "3V3_17") (pintype "input"))
    )
    (net (code "40") (name "unconnected-(U1-A6-Pad25)") (class "Default")
      (node (ref "U1") (pin "25") (pinfunction "A6_25") (pintype "input"))
    )
    (net (code "41") (name "unconnected-(U1-A7-Pad26)") (class "Default")
      (node (ref "U1") (pin "26") (pinfunction "A7_26") (pintype "input"))
    )
    (net (code "42") (name "unconnected-(U1-AREF-Pad18)") (class "Default")
      (node (ref "U1") (pin "18") (pinfunction "AREF_18") (pintype "input"))
    )
    (net (code "43") (name "unconnected-(U1-D0{slash}RX-Pad2)") (class "Default")
      (node (ref "U1") (pin "2") (pinfunction "D0/RX_2") (pintype "input"))
    )
    (net (code "44") (name "unconnected-(U1-D1{slash}TX-Pad1)") (class "Default")
      (node (ref "U1") (pin "1") (pinfunction "D1/TX_1") (pintype "input"))
    )
    (net (code "45") (name "unconnected-(U1-RESET-Pad3)") (class "Default")
      (node (ref "U1") (pin "3") (pinfunction "RESET_3") (pintype "input"))
    )
    (net (code "46") (name "unconnected-(U2-Pad10)") (class "Default")
      (node (ref "U2") (pin "10") (pinfunction "10_10") (pintype "input"))
    )
    (net (code "47") (name "unconnected-(U7-CLKOUT{slash}SOF-Pad3)") (class "Default")
      (node (ref "U7") (pin "3") (pinfunction "CLKOUT/SOF_3") (pintype "input"))
    )
    (net (code "48") (name "unconnected-(U7-NC-Pad6)") (class "Default")
      (node (ref "U7") (pin "6") (pinfunction "NC_6") (pintype "input"))
    )
    (net (code "49") (name "unconnected-(U7-NC-Pad15)") (class "Default")
      (node (ref "U7") (pin "15") (pinfunction "NC_15") (pintype "input"))
    )
    (net (code "50") (name "unconnected-(U7-RX0BF#-Pad12)") (class "Default")
      (node (ref "U7") (pin "12") (pinfunction "RX0BF#_12") (pintype "input"))
    )
    (net (code "51") (name "unconnected-(U7-RX1BF#-Pad11)") (class "Default")
      (node (ref "U7") (pin "11") (pinfunction "RX1BF#_11") (pintype "input"))
    )
    (net (code "52") (name "unconnected-(U7-TX0RTS#-Pad4)") (class "Default")
      (node (ref "U7") (pin "4") (pinfunction "TX0RTS#_4") (pintype "input"))
    )
    (net (code "53") (name "unconnected-(U7-TX1RTS#-Pad5)") (class "Default")
      (node (ref "U7") (pin "5") (pinfunction "TX1RTS#_5") (pintype "input"))
    )
    (net (code "54") (name "unconnected-(U7-TX2RTS#-Pad7)") (class "Default")
      (node (ref "U7") (pin "7") (pinfunction "TX2RTS#_7") (pintype "input"))
    )
    (net (code "55") (name "unconnected-(U8-VREF-Pad5)") (class "Default")
      (node (ref "U8") (pin "5") (pinfunction "VREF_5") (pintype "input"))
    )
    (net (code "56") (name "unconnected-(U10-GND-Pad2)") (class "Default")
      (node (ref "U10") (pin "2") (pinfunction "GND_2") (pintype "input"))
    )
    (net (code "57") (name "unconnected-(U10-GND-Pad4)") (class "Default")
      (node (ref "U10") (pin "4") (pinfunction "GND_4") (pintype "input"))
    )
  )
)
